# HEBoard_schematic.net
KiCad netlist of a schematic drawn in Altium Designer
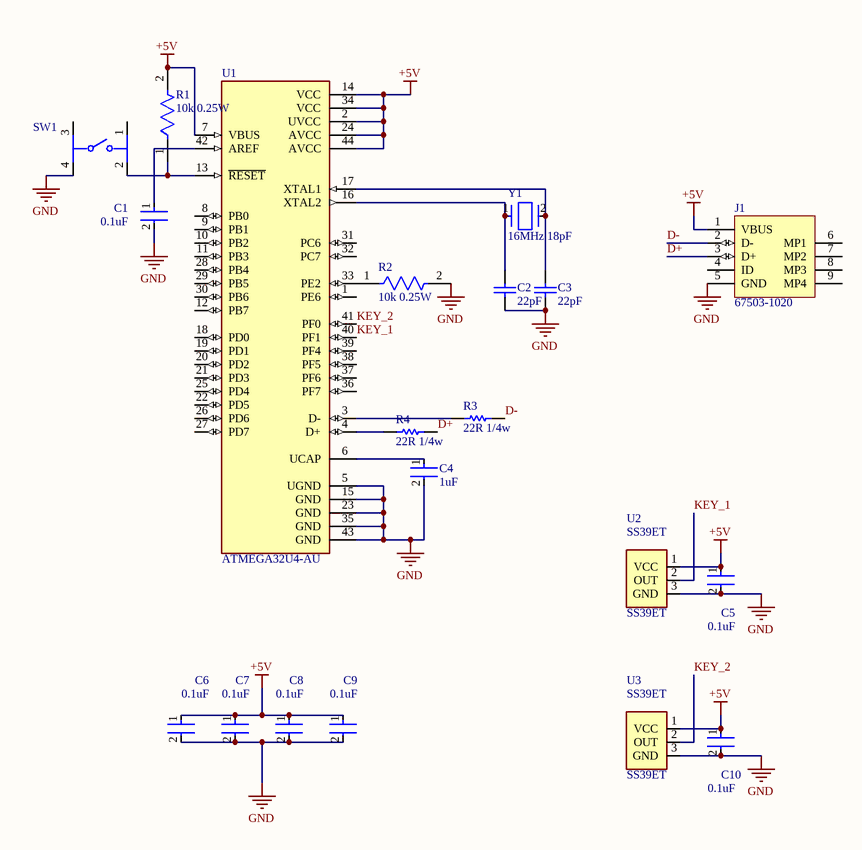
[diagram p0: HEBoard_schematic.SchDoc]

(export (version "E")
  (design (tool "Eeschema 10.0.6"))
  (components
    (comp (ref "C1")
      (value "0.1uF")
      (footprint "FP-GRM033-0_03-IPC_C")
      (description "Chip Multilayer Ceramic Capacitors for General Purpose, 0201, 0.10uF, X5R, 15%, 10%, 10V")
      (fields (field (name "TOLERANCE") "10%") (field (name "VOLTAGE") "10V"))
      (libsource (lib "Altium Content Vault") (part "b4654b650e69147ec39a6b967a45e02"))
    )
    (comp (ref "C2")
      (value "22pF")
      (footprint "CAPC1006X50X20ML10T10")
      (fields
        (field (name "PART NUMBER") "0402ZK220GBSTR..")
        (field (name "MANUFACTURER") "AVX Interconnect / Elco")
      )
      (libsource (lib "Altium Content Vault") (part "CAP"))
    )
    (comp (ref "C3")
      (value "22pF")
      (footprint "CAPC1006X50X20ML10T10")
      (fields
        (field (name "PART NUMBER") "0402ZK220GBSTR..")
        (field (name "MANUFACTURER") "AVX Interconnect / Elco")
      )
      (libsource (lib "Altium Content Vault") (part "CAP"))
    )
    (comp (ref "C4")
      (value "1uF")
      (footprint "FP-GRM15-0_1-MFG")
      (description "CAP CER 1UF 10V X5R 0402")
      (fields
        (field (name "OCTOPART") "https://octopart.com/grm155r61a105ke15d-murata-197442")
        (field (name "MANUFACTURER PART NUMBER") "GRM155R61A105KE15D")
      )
      (libsource (lib "Altium Content Vault") (part "02cd4be3c70576c341d710602a673aa"))
    )
    (comp (ref "C5")
      (value "0.1uF")
      (footprint "FP-GRM033-0_03-IPC_C")
      (description "Chip Multilayer Ceramic Capacitors for General Purpose, 0201, 0.10uF, X5R, 15%, 10%, 10V")
      (fields (field (name "TOLERANCE") "10%") (field (name "VOLTAGE") "10V"))
      (libsource (lib "Altium Content Vault") (part "b4654b650e69147ec39a6b967a45e02"))
    )
    (comp (ref "C6")
      (value "0.1uF")
      (footprint "FP-GRM033-0_03-IPC_C")
      (description "Chip Multilayer Ceramic Capacitors for General Purpose, 0201, 0.10uF, X5R, 15%, 10%, 10V")
      (fields (field (name "TOLERANCE") "10%") (field (name "VOLTAGE") "10V"))
      (libsource (lib "Altium Content Vault") (part "b4654b650e69147ec39a6b967a45e02"))
    )
    (comp (ref "C7")
      (value "0.1uF")
      (footprint "FP-GRM033-0_03-IPC_C")
      (description "Chip Multilayer Ceramic Capacitors for General Purpose, 0201, 0.10uF, X5R, 15%, 10%, 10V")
      (fields (field (name "TOLERANCE") "10%") (field (name "VOLTAGE") "10V"))
      (libsource (lib "Altium Content Vault") (part "b4654b650e69147ec39a6b967a45e02"))
    )
    (comp (ref "C8")
      (value "0.1uF")
      (footprint "FP-GRM033-0_03-IPC_C")
      (description "Chip Multilayer Ceramic Capacitors for General Purpose, 0201, 0.10uF, X5R, 15%, 10%, 10V")
      (fields (field (name "TOLERANCE") "10%") (field (name "VOLTAGE") "10V"))
      (libsource (lib "Altium Content Vault") (part "b4654b650e69147ec39a6b967a45e02"))
    )
    (comp (ref "C9")
      (value "0.1uF")
      (footprint "FP-GRM033-0_03-IPC_C")
      (description "Chip Multilayer Ceramic Capacitors for General Purpose, 0201, 0.10uF, X5R, 15%, 10%, 10V")
      (fields (field (name "TOLERANCE") "10%") (field (name "VOLTAGE") "10V"))
      (libsource (lib "Altium Content Vault") (part "b4654b650e69147ec39a6b967a45e02"))
    )
    (comp (ref "C10")
      (value "0.1uF")
      (footprint "FP-GRM033-0_03-IPC_C")
      (description "Chip Multilayer Ceramic Capacitors for General Purpose, 0201, 0.10uF, X5R, 15%, 10%, 10V")
      (fields (field (name "TOLERANCE") "10%") (field (name "VOLTAGE") "10V"))
      (libsource (lib "Altium Content Vault") (part "b4654b650e69147ec39a6b967a45e02"))
    )
    (comp (ref "J1")
      (value "67503-1020")
      (footprint "MOLX-67503-1020_V")
      (description "USB, MINI, SMD, RA KME04-USBMU03A01")
      (fields (field (name "MANUFACTURER") "Molex"))
      (libsource (lib "Altium Content Vault") (part "MOLX-67503-1020"))
    )
    (comp (ref "R1")
      (value "10k 0.25W")
      (footprint "FP-RNCP0805-IPC_C")
      (description "10kΩ ±1% 0.25W 0805 High Power Anti-Sulfur Thin Film Chip Resistor")
      (fields (field (name "TOLERANCE") "1%"))
      (libsource (lib "Altium Content Vault") (part "1029c3af85768c4190bb7ad29bc67b5"))
    )
    (comp (ref "R2")
      (value "10k 0.25W")
      (footprint "FP-RNCP0805-IPC_C")
      (description "10kΩ ±1% 0.25W 0805 High Power Anti-Sulfur Thin Film Chip Resistor")
      (fields (field (name "TOLERANCE") "1%"))
      (libsource (lib "Altium Content Vault") (part "1029c3af85768c4190bb7ad29bc67b5"))
    )
    (comp (ref "R3")
      (value "22R 1/4w")
      (footprint "RESC3216X60X45LL10T20")
      (fields (field (name "PART NUMBER") "CRCW120622R0JNEA") (field (name "MANUFACTURER") "Vishay Dale"))
      (libsource (lib "Altium Content Vault") (part "RES"))
    )
    (comp (ref "R4")
      (value "22R 1/4w")
      (footprint "RESC3216X60X45LL10T20")
      (fields (field (name "PART NUMBER") "CRCW120622R0JNEA") (field (name "MANUFACTURER") "Vishay Dale"))
      (libsource (lib "Altium Content Vault") (part "RES"))
    )
    (comp (ref "SW1")
      (value "~")
      (footprint "FP-PTS645SM43SMTR92LFS-MFG")
      (description "SWITCH TACTILE SPST-NO 0.05A 12V")
      (libsource (lib "Altium Content Vault") (part "1adf0dd01260c80cf25a44bfd6b99ba"))
    )
    (comp (ref "U1")
      (value "ATMEGA32U4-AU")
      (footprint "QFP80P1200X1200X120-44N")
      (description "AVR AVRÂ® ATmega Microcontroller IC 8-Bit 16MHz 32KB (16K x 16) FLASH 44-TQFP (10x10)")
      (fields (field (name "MF") "Microchip Technology"))
      (libsource (lib "Schlib1") (part "ATMEGA32U4-AU"))
    )
    (comp (ref "U2")
      (value "SS39ET")
      (footprint "CHRY-MX1A-11NW_V")
      (description "analog Hall Effect Sensor 1.5 mA 2.7 - 6.5 V dc ¦ Honeywell SS39ET")
      (fields (field (name "MF") "Honeywell Sensing and Productivity Solutions"))
      (libsource (lib "Schlib1") (part "SS39ET"))
    )
    (comp (ref "U3")
      (value "SS39ET")
      (footprint "CHRY-MX1A-11NW_V")
      (description "analog Hall Effect Sensor 1.5 mA 2.7 - 6.5 V dc ¦ Honeywell SS39ET")
      (fields (field (name "MF") "Honeywell Sensing and Productivity Solutions"))
      (libsource (lib "Schlib1") (part "SS39ET"))
    )
    (comp (ref "Y1")
      (value "16MHz 18pF")
      (footprint "FP-ABM7-MFG")
      (description "Crystal 16MHz ±20ppm 18pF SMD-2 6mm x 3.5mm")
      (fields (field (name "TOLERANCE") "20ppm"))
      (libsource (lib "Altium Content Vault") (part "c23a69dc6c9e2f18f2079038eb95dd1"))
    )
  )
  (nets
    (net (code "1") (name "+5V") (class "Default")
      (node (ref "C10") (pin "1") (pinfunction "1_1") (pintype "passive"))
      (node (ref "C5") (pin "1") (pinfunction "1_1") (pintype "passive"))
      (node (ref "C6") (pin "1") (pinfunction "1_1") (pintype "passive"))
      (node (ref "C7") (pin "1") (pinfunction "1_1") (pintype "passive"))
      (node (ref "C8") (pin "1") (pinfunction "1_1") (pintype "passive"))
      (node (ref "C9") (pin "1") (pinfunction "1_1") (pintype "passive"))
      (node (ref "J1") (pin "1") (pinfunction "VBUS_1") (pintype "power_in"))
      (node (ref "R1") (pin "2") (pinfunction "2_2") (pintype "passive"))
      (node (ref "U1") (pin "14") (pinfunction "VCC_14") (pintype "power_in"))
      (node (ref "U1") (pin "2") (pinfunction "UVCC_2") (pintype "power_in"))
      (node (ref "U1") (pin "24") (pinfunction "AVCC_24") (pintype "power_in"))
      (node (ref "U1") (pin "34") (pinfunction "VCC_34") (pintype "power_in"))
      (node (ref "U1") (pin "44") (pinfunction "AVCC_44") (pintype "power_in"))
      (node (ref "U1") (pin "7") (pinfunction "VBUS_7") (pintype "input"))
      (node (ref "U2") (pin "1") (pinfunction "VCC_1") (pintype "passive"))
      (node (ref "U3") (pin "1") (pinfunction "VCC_1") (pintype "passive"))
    )
    (net (code "2") (name "/D+") (class "Default")
      (node (ref "J1") (pin "3") (pinfunction "D+_3") (pintype "bidirectional"))
      (node (ref "R4") (pin "2") (pinfunction "2_2") (pintype "passive"))
    )
    (net (code "3") (name "/D-") (class "Default")
      (node (ref "J1") (pin "2") (pinfunction "D-_2") (pintype "bidirectional"))
      (node (ref "R3") (pin "2") (pinfunction "2_2") (pintype "passive"))
    )
    (net (code "4") (name "/KEY_1") (class "Default")
      (node (ref "U1") (pin "40") (pinfunction "PF1_40") (pintype "bidirectional"))
      (node (ref "U2") (pin "2") (pinfunction "OUT_2") (pintype "passive"))
    )
    (net (code "5") (name "/KEY_2") (class "Default")
      (node (ref "U1") (pin "41") (pinfunction "PF0_41") (pintype "bidirectional"))
      (node (ref "U3") (pin "2") (pinfunction "OUT_2") (pintype "passive"))
    )
    (net (code "6") (name "GND") (class "Default")
      (node (ref "C1") (pin "2") (pinfunction "2_2") (pintype "passive"))
      (node (ref "C10") (pin "2") (pinfunction "2_2") (pintype "passive"))
      (node (ref "C2") (pin "1") (pinfunction "1_1") (pintype "passive"))
      (node (ref "C3") (pin "1") (pinfunction "1_1") (pintype "passive"))
      (node (ref "C4") (pin "2") (pinfunction "2_2") (pintype "passive"))
      (node (ref "C5") (pin "2") (pinfunction "2_2") (pintype "passive"))
      (node (ref "C6") (pin "2") (pinfunction "2_2") (pintype "passive"))
      (node (ref "C7") (pin "2") (pinfunction "2_2") (pintype "passive"))
      (node (ref "C8") (pin "2") (pinfunction "2_2") (pintype "passive"))
      (node (ref "C9") (pin "2") (pinfunction "2_2") (pintype "passive"))
      (node (ref "J1") (pin "5") (pinfunction "GND_5") (pintype "power_in"))
      (node (ref "R2") (pin "2") (pinfunction "2_2") (pintype "passive"))
      (node (ref "SW1") (pin "4") (pinfunction "4_4") (pintype "passive"))
      (node (ref "U1") (pin "15") (pinfunction "GND_15") (pintype "power_in"))
      (node (ref "U1") (pin "23") (pinfunction "GND_23") (pintype "power_in"))
      (node (ref "U1") (pin "35") (pinfunction "GND_35") (pintype "power_in"))
      (node (ref "U1") (pin "43") (pinfunction "GND_43") (pintype "power_in"))
      (node (ref "U1") (pin "5") (pinfunction "UGND_5") (pintype "power_in"))
      (node (ref "U2") (pin "3") (pinfunction "GND_3") (pintype "passive"))
      (node (ref "U3") (pin "3") (pinfunction "GND_3") (pintype "passive"))
    )
    (net (code "7") (name "Net-(U1-AREF)") (class "Default")
      (node (ref "C1") (pin "1") (pinfunction "1_1") (pintype "passive"))
      (node (ref "U1") (pin "42") (pinfunction "AREF_42") (pintype "input"))
    )
    (net (code "8") (name "Net-(U1-D+)") (class "Default")
      (node (ref "R4") (pin "1") (pinfunction "1_1") (pintype "passive"))
      (node (ref "U1") (pin "4") (pinfunction "D+_4") (pintype "bidirectional"))
    )
    (net (code "9") (name "Net-(U1-D-)") (class "Default")
      (node (ref "R3") (pin "1") (pinfunction "1_1") (pintype "passive"))
      (node (ref "U1") (pin "3") (pinfunction "D-_3") (pintype "bidirectional"))
    )
    (net (code "10") (name "Net-(U1-PE2)") (class "Default")
      (node (ref "R2") (pin "1") (pinfunction "1_1") (pintype "passive"))
      (node (ref "U1") (pin "33") (pinfunction "PE2_33") (pintype "bidirectional"))
    )
    (net (code "11") (name "Net-(U1-UCAP)") (class "Default")
      (node (ref "C4") (pin "1") (pinfunction "1_1") (pintype "passive"))
      (node (ref "U1") (pin "6") (pinfunction "UCAP_6") (pintype "passive"))
    )
    (net (code "12") (name "Net-(U1-XTAL1)") (class "Default")
      (node (ref "C3") (pin "2") (pinfunction "2_2") (pintype "passive"))
      (node (ref "U1") (pin "17") (pinfunction "XTAL1_17") (pintype "input"))
      (node (ref "Y1") (pin "2") (pinfunction "2_2") (pintype "passive"))
    )
    (net (code "13") (name "Net-(U1-XTAL2)") (class "Default")
      (node (ref "C2") (pin "2") (pinfunction "2_2") (pintype "passive"))
      (node (ref "U1") (pin "16") (pinfunction "XTAL2_16") (pintype "output"))
      (node (ref "Y1") (pin "1") (pinfunction "1_1") (pintype "passive"))
    )
    (net (code "14") (name "Net-(U1-~{RESET})") (class "Default")
      (node (ref "R1") (pin "1") (pinfunction "1_1") (pintype "passive"))
      (node (ref "SW1") (pin "2") (pinfunction "2_2") (pintype "passive"))
      (node (ref "U1") (pin "13") (pinfunction "~{RESET}_13") (pintype "input"))
    )
    (net (code "15") (name "unconnected-(J1-ID-Pad4)") (class "Default")
      (node (ref "J1") (pin "4") (pinfunction "ID_4") (pintype "passive"))
    )
    (net (code "16") (name "unconnected-(J1-MP1-Pad6)") (class "Default")
      (node (ref "J1") (pin "6") (pinfunction "MP1_6") (pintype "passive"))
    )
    (net (code "17") (name "unconnected-(J1-MP2-Pad7)") (class "Default")
      (node (ref "J1") (pin "7") (pinfunction "MP2_7") (pintype "passive"))
    )
    (net (code "18") (name "unconnected-(J1-MP3-Pad8)") (class "Default")
      (node (ref "J1") (pin "8") (pinfunction "MP3_8") (pintype "passive"))
    )
    (net (code "19") (name "unconnected-(J1-MP4-Pad9)") (class "Default")
      (node (ref "J1") (pin "9") (pinfunction "MP4_9") (pintype "passive"))
    )
    (net (code "20") (name "unconnected-(SW1-Pad1)") (class "Default")
      (node (ref "SW1") (pin "1") (pinfunction "1_1") (pintype "passive"))
    )
    (net (code "21") (name "unconnected-(SW1-Pad3)") (class "Default")
      (node (ref "SW1") (pin "3") (pinfunction "3_3") (pintype "passive"))
    )
    (net (code "22") (name "unconnected-(U1-PB0-Pad8)") (class "Default")
      (node (ref "U1") (pin "8") (pinfunction "PB0_8") (pintype "bidirectional"))
    )
    (net (code "23") (name "unconnected-(U1-PB1-Pad9)") (class "Default")
      (node (ref "U1") (pin "9") (pinfunction "PB1_9") (pintype "bidirectional"))
    )
    (net (code "24") (name "unconnected-(U1-PB2-Pad10)") (class "Default")
      (node (ref "U1") (pin "10") (pinfunction "PB2_10") (pintype "bidirectional"))
    )
    (net (code "25") (name "unconnected-(U1-PB3-Pad11)") (class "Default")
      (node (ref "U1") (pin "11") (pinfunction "PB3_11") (pintype "bidirectional"))
    )
    (net (code "26") (name "unconnected-(U1-PB4-Pad28)") (class "Default")
      (node (ref "U1") (pin "28") (pinfunction "PB4_28") (pintype "bidirectional"))
    )
    (net (code "27") (name "unconnected-(U1-PB5-Pad29)") (class "Default")
      (node (ref "U1") (pin "29") (pinfunction "PB5_29") (pintype "bidirectional"))
    )
    (net (code "28") (name "unconnected-(U1-PB6-Pad30)") (class "Default")
      (node (ref "U1") (pin "30") (pinfunction "PB6_30") (pintype "bidirectional"))
    )
    (net (code "29") (name "unconnected-(U1-PB7-Pad12)") (class "Default")
      (node (ref "U1") (pin "12") (pinfunction "PB7_12") (pintype "bidirectional"))
    )
    (net (code "30") (name "unconnected-(U1-PC6-Pad31)") (class "Default")
      (node (ref "U1") (pin "31") (pinfunction "PC6_31") (pintype "bidirectional"))
    )
    (net (code "31") (name "unconnected-(U1-PC7-Pad32)") (class "Default")
      (node (ref "U1") (pin "32") (pinfunction "PC7_32") (pintype "bidirectional"))
    )
    (net (code "32") (name "unconnected-(U1-PD0-Pad18)") (class "Default")
      (node (ref "U1") (pin "18") (pinfunction "PD0_18") (pintype "bidirectional"))
    )
    (net (code "33") (name "unconnected-(U1-PD1-Pad19)") (class "Default")
      (node (ref "U1") (pin "19") (pinfunction "PD1_19") (pintype "bidirectional"))
    )
    (net (code "34") (name "unconnected-(U1-PD2-Pad20)") (class "Default")
      (node (ref "U1") (pin "20") (pinfunction "PD2_20") (pintype "bidirectional"))
    )
    (net (code "35") (name "unconnected-(U1-PD3-Pad21)") (class "Default")
      (node (ref "U1") (pin "21") (pinfunction "PD3_21") (pintype "bidirectional"))
    )
    (net (code "36") (name "unconnected-(U1-PD4-Pad25)") (class "Default")
      (node (ref "U1") (pin "25") (pinfunction "PD4_25") (pintype "bidirectional"))
    )
    (net (code "37") (name "unconnected-(U1-PD5-Pad22)") (class "Default")
      (node (ref "U1") (pin "22") (pinfunction "PD5_22") (pintype "bidirectional"))
    )
    (net (code "38") (name "unconnected-(U1-PD6-Pad26)") (class "Default")
      (node (ref "U1") (pin "26") (pinfunction "PD6_26") (pintype "bidirectional"))
    )
    (net (code "39") (name "unconnected-(U1-PD7-Pad27)") (class "Default")
      (node (ref "U1") (pin "27") (pinfunction "PD7_27") (pintype "bidirectional"))
    )
    (net (code "40") (name "unconnected-(U1-PE6-Pad1)") (class "Default")
      (node (ref "U1") (pin "1") (pinfunction "PE6_1") (pintype "bidirectional"))
    )
    (net (code "41") (name "unconnected-(U1-PF4-Pad39)") (class "Default")
      (node (ref "U1") (pin "39") (pinfunction "PF4_39") (pintype "bidirectional"))
    )
    (net (code "42") (name "unconnected-(U1-PF5-Pad38)") (class "Default")
      (node (ref "U1") (pin "38") (pinfunction "PF5_38") (pintype "bidirectional"))
    )
    (net (code "43") (name "unconnected-(U1-PF6-Pad37)") (class "Default")
      (node (ref "U1") (pin "37") (pinfunction "PF6_37") (pintype "bidirectional"))
    )
    (net (code "44") (name "unconnected-(U1-PF7-Pad36)") (class "Default")
      (node (ref "U1") (pin "36") (pinfunction "PF7_36") (pintype "bidirectional"))
    )
  )
)
